# SDIO_SPDT_TX02612.net
KiCad netlist of a schematic drawn in Altium Designer
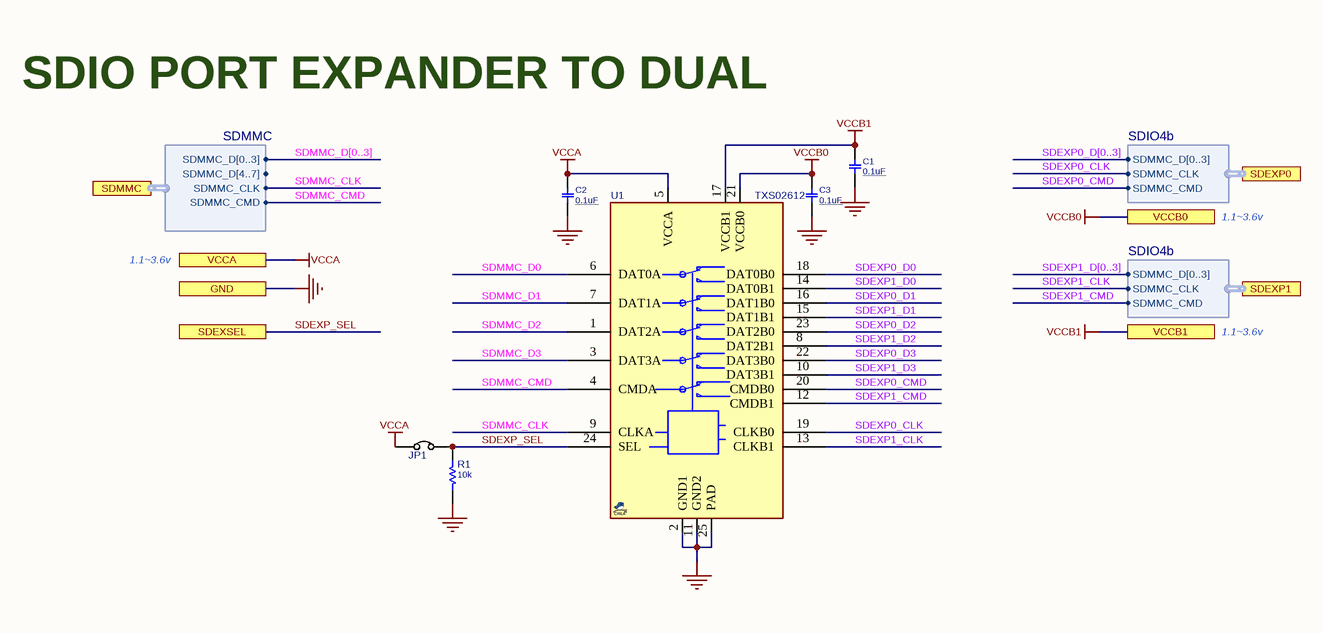
[diagram p0: SDIO_SPDT_TX02612.SchDoc]

(export (version "E")
  (design (tool "Eeschema 10.0.6"))
  (components
    (comp (ref "C1")
      (value "0.1uF")
      (footprint "C0402")
      (description "CAP, MLCC")
      (fields (field (name "MANF_P#") "MANF_PART#") (field (name "MANF") "Murata"))
      (libsource (lib "passive_smd") (part "CAP_SMD_MLCC"))
    )
    (comp (ref "C2")
      (value "0.1uF")
      (footprint "C0402")
      (description "CAP, MLCC")
      (fields (field (name "MANF_P#") "MANF_PART#") (field (name "MANF") "Murata"))
      (libsource (lib "passive_smd") (part "CAP_SMD_MLCC"))
    )
    (comp (ref "C3")
      (value "0.1uF")
      (footprint "C0402")
      (description "CAP, MLCC")
      (fields (field (name "MANF_P#") "MANF_PART#") (field (name "MANF") "Murata"))
      (libsource (lib "passive_smd") (part "CAP_SMD_MLCC"))
    )
    (comp (ref "JP1")
      (value "JMPSOLDER")
      (footprint "JP_60X100")
      (description "JUMPER, HEADER 2PIN")
      (fields (field (name "MANF") "MANF") (field (name "MANF_P#") "MANF_P#"))
      (libsource (lib "test-tp_jumper") (part "JUMPER_SOLDER"))
    )
    (comp (ref "R1")
      (value "10k")
      (footprint "R0402")
      (description "RESISTOR, SMD")
      (libsource (lib "passive_res_smd") (part "RES_SMD"))
    )
    (comp (ref "U1")
      (value "TXS02612")
      (footprint "QFN50_24T")
      (description "I/O Expander, SDIO")
      (fields (field (name "MANF") "Texas Instruments") (field (name "MANF_P#") "TXS02612RTWR"))
      (libsource (lib "buffer_digital") (part "TXS02612_QFN24"))
    )
  )
  (nets
    (net (code "3") (name "/SDEXP0_CLK") (class "Default")
      (node (ref "U1") (pin "19") (pinfunction "CLKB0_19") (pintype "passive"))
    )
    (net (code "4") (name "/SDEXP0_CMD") (class "Default")
      (node (ref "U1") (pin "20") (pinfunction "CMDB0_20") (pintype "passive"))
    )
    (net (code "5") (name "/SDEXP0_D0") (class "Default")
      (node (ref "U1") (pin "18") (pinfunction "DAT0B0_18") (pintype "passive"))
    )
    (net (code "6") (name "/SDEXP0_D1") (class "Default")
      (node (ref "U1") (pin "16") (pinfunction "DAT1B0_16") (pintype "passive"))
    )
    (net (code "7") (name "/SDEXP0_D2") (class "Default")
      (node (ref "U1") (pin "23") (pinfunction "DAT2B0_23") (pintype "passive"))
    )
    (net (code "8") (name "/SDEXP0_D3") (class "Default")
      (node (ref "U1") (pin "22") (pinfunction "DAT3B0_22") (pintype "passive"))
    )
    (net (code "10") (name "/SDEXP1_CLK") (class "Default")
      (node (ref "U1") (pin "13") (pinfunction "CLKB1_13") (pintype "passive"))
    )
    (net (code "11") (name "/SDEXP1_CMD") (class "Default")
      (node (ref "U1") (pin "12") (pinfunction "CMDB1_12") (pintype "passive"))
    )
    (net (code "12") (name "/SDEXP1_D0") (class "Default")
      (node (ref "U1") (pin "14") (pinfunction "DAT0B1_14") (pintype "passive"))
    )
    (net (code "13") (name "/SDEXP1_D1") (class "Default")
      (node (ref "U1") (pin "15") (pinfunction "DAT1B1_15") (pintype "passive"))
    )
    (net (code "14") (name "/SDEXP1_D2") (class "Default")
      (node (ref "U1") (pin "8") (pinfunction "DAT2B1_8") (pintype "passive"))
    )
    (net (code "15") (name "/SDEXP1_D3") (class "Default")
      (node (ref "U1") (pin "10") (pinfunction "DAT3B1_10") (pintype "passive"))
    )
    (net (code "17") (name "/SDEXP_SEL") (class "Default")
      (node (ref "JP1") (pin "1") (pinfunction "1_1") (pintype "passive"))
      (node (ref "R1") (pin "1") (pinfunction "1_1") (pintype "passive"))
      (node (ref "U1") (pin "24") (pinfunction "SEL_24") (pintype "passive"))
    )
    (net (code "18") (name "/SDMMC_CLK") (class "Default")
      (node (ref "U1") (pin "9") (pinfunction "CLKA_9") (pintype "passive"))
    )
    (net (code "19") (name "/SDMMC_CMD") (class "Default")
      (node (ref "U1") (pin "4") (pinfunction "CMDA_4") (pintype "passive"))
    )
    (net (code "20") (name "/SDMMC_D0") (class "Default")
      (node (ref "U1") (pin "6") (pinfunction "DAT0A_6") (pintype "passive"))
    )
    (net (code "21") (name "/SDMMC_D1") (class "Default")
      (node (ref "U1") (pin "7") (pinfunction "DAT1A_7") (pintype "passive"))
    )
    (net (code "22") (name "/SDMMC_D2") (class "Default")
      (node (ref "U1") (pin "1") (pinfunction "DAT2A_1") (pintype "passive"))
    )
    (net (code "23") (name "/SDMMC_D3") (class "Default")
      (node (ref "U1") (pin "3") (pinfunction "DAT3A_3") (pintype "passive"))
    )
    (net (code "27") (name "GND") (class "Default")
      (node (ref "C1") (pin "2") (pinfunction "2_2") (pintype "passive"))
      (node (ref "C2") (pin "2") (pinfunction "2_2") (pintype "passive"))
      (node (ref "C3") (pin "2") (pinfunction "2_2") (pintype "passive"))
      (node (ref "R1") (pin "2") (pinfunction "2_2") (pintype "passive"))
      (node (ref "U1") (pin "11") (pinfunction "GND2_11") (pintype "passive"))
      (node (ref "U1") (pin "2") (pinfunction "GND1_2") (pintype "passive"))
      (node (ref "U1") (pin "25") (pinfunction "PAD_25") (pintype "passive"))
    )
    (net (code "28") (name "VCCA") (class "Default")
      (node (ref "C2") (pin "1") (pinfunction "1_1") (pintype "passive"))
      (node (ref "JP1") (pin "2") (pinfunction "2_2") (pintype "passive"))
      (node (ref "U1") (pin "5") (pinfunction "VCCA_5") (pintype "passive"))
    )
    (net (code "29") (name "VCCB0") (class "Default")
      (node (ref "C3") (pin "1") (pinfunction "1_1") (pintype "passive"))
      (node (ref "U1") (pin "21") (pinfunction "VCCB0_21") (pintype "passive"))
    )
    (net (code "30") (name "VCCB1") (class "Default")
      (node (ref "C1") (pin "1") (pinfunction "1_1") (pintype "passive"))
      (node (ref "U1") (pin "17") (pinfunction "VCCB1_17") (pintype "passive"))
    )
  )
)
